# principal.net
KiCad netlist of a schematic drawn in EAGLE
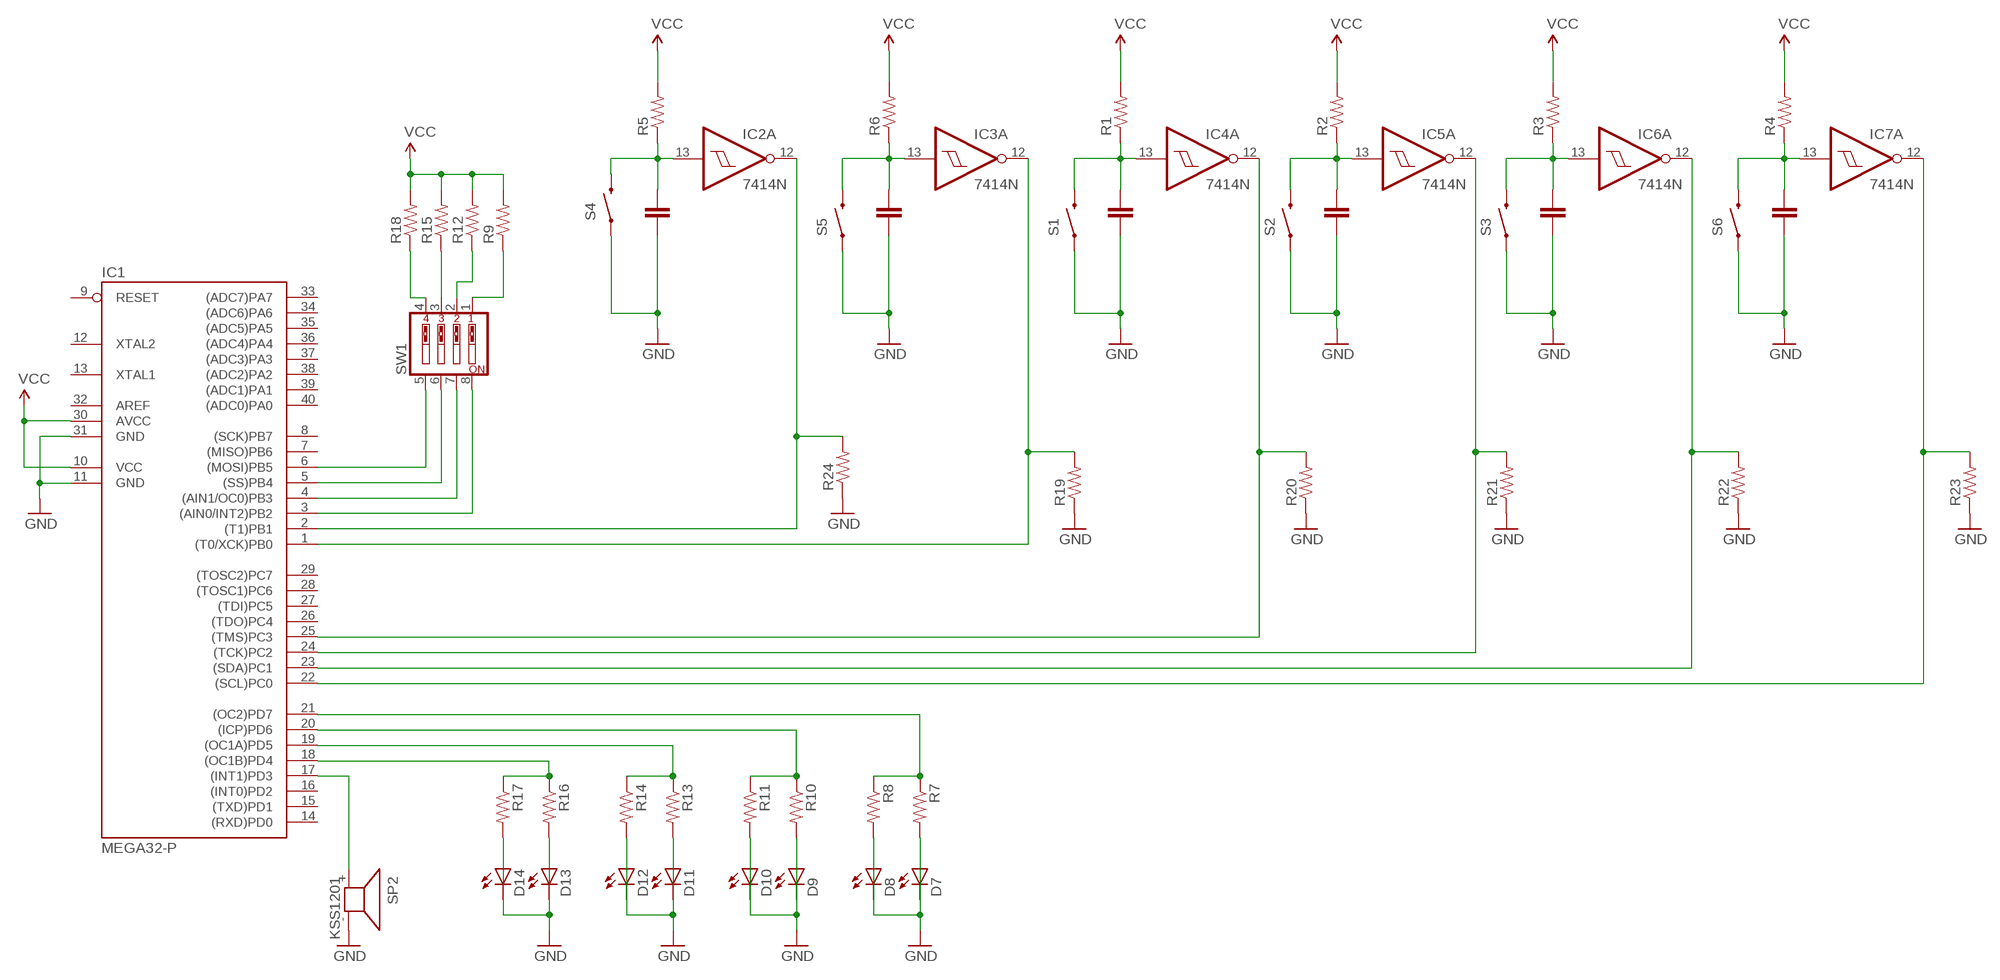
[diagram p0: schematic, sheet 1]

(export (version "E")
  (design (tool "Eeschema 10.0.6"))
  (components
    (comp (ref "D7")
      (value "LED5MM")
      (footprint "eagle-import:LED5MM")
      (libsource (lib "eagle-import") (part "LED5MM"))
    )
    (comp (ref "D8")
      (value "LED5MM")
      (footprint "eagle-import:LED5MM")
      (libsource (lib "eagle-import") (part "LED5MM"))
    )
    (comp (ref "D9")
      (value "LED5MM")
      (footprint "eagle-import:LED5MM")
      (libsource (lib "eagle-import") (part "LED5MM"))
    )
    (comp (ref "D10")
      (value "LED5MM")
      (footprint "eagle-import:LED5MM")
      (libsource (lib "eagle-import") (part "LED5MM"))
    )
    (comp (ref "D11")
      (value "LED5MM")
      (footprint "eagle-import:LED5MM")
      (libsource (lib "eagle-import") (part "LED5MM"))
    )
    (comp (ref "D12")
      (value "LED5MM")
      (footprint "eagle-import:LED5MM")
      (libsource (lib "eagle-import") (part "LED5MM"))
    )
    (comp (ref "D13")
      (value "LED5MM")
      (footprint "eagle-import:LED5MM")
      (libsource (lib "eagle-import") (part "LED5MM"))
    )
    (comp (ref "D14")
      (value "LED5MM")
      (footprint "eagle-import:LED5MM")
      (libsource (lib "eagle-import") (part "LED5MM"))
    )
    (comp (ref "IC1")
      (value "MEGA32-P")
      (footprint "eagle-import:DIL40")
      (fields (field (name "MPN") "ATMEGA32-16PU"))
      (libsource (lib "eagle-import") (part "MEGA32-P"))
    )
    (comp (ref "IC2")
      (value "7414N")
      (footprint "eagle-import:DIL14")
      (libsource (lib "eagle-import") (part "7414N"))
    )
    (comp (ref "IC3")
      (value "7414N")
      (footprint "eagle-import:DIL14")
      (libsource (lib "eagle-import") (part "7414N"))
    )
    (comp (ref "IC4")
      (value "7414N")
      (footprint "eagle-import:DIL14")
      (libsource (lib "eagle-import") (part "7414N"))
    )
    (comp (ref "IC5")
      (value "7414N")
      (footprint "eagle-import:DIL14")
      (libsource (lib "eagle-import") (part "7414N"))
    )
    (comp (ref "IC6")
      (value "7414N")
      (footprint "eagle-import:DIL14")
      (libsource (lib "eagle-import") (part "7414N"))
    )
    (comp (ref "IC7")
      (value "7414N")
      (footprint "eagle-import:DIL14")
      (libsource (lib "eagle-import") (part "7414N"))
    )
    (comp (ref "R1")
      (value "R-US_0204/5")
      (footprint "eagle-import:0204_5")
      (libsource (lib "eagle-import") (part "R-US_0204/5"))
    )
    (comp (ref "R2")
      (value "R-US_0204/5")
      (footprint "eagle-import:0204_5")
      (libsource (lib "eagle-import") (part "R-US_0204/5"))
    )
    (comp (ref "R3")
      (value "R-US_0204/5")
      (footprint "eagle-import:0204_5")
      (libsource (lib "eagle-import") (part "R-US_0204/5"))
    )
    (comp (ref "R4")
      (value "R-US_0204/5")
      (footprint "eagle-import:0204_5")
      (libsource (lib "eagle-import") (part "R-US_0204/5"))
    )
    (comp (ref "R5")
      (value "R-US_0204/5")
      (footprint "eagle-import:0204_5")
      (libsource (lib "eagle-import") (part "R-US_0204/5"))
    )
    (comp (ref "R6")
      (value "R-US_0204/5")
      (footprint "eagle-import:0204_5")
      (libsource (lib "eagle-import") (part "R-US_0204/5"))
    )
    (comp (ref "R7")
      (value "R-US_0204/5")
      (footprint "eagle-import:0204_5")
      (libsource (lib "eagle-import") (part "R-US_0204/5"))
    )
    (comp (ref "R8")
      (value "R-US_0204/5")
      (footprint "eagle-import:0204_5")
      (libsource (lib "eagle-import") (part "R-US_0204/5"))
    )
    (comp (ref "R9")
      (value "R-US_0204/5")
      (footprint "eagle-import:0204_5")
      (libsource (lib "eagle-import") (part "R-US_0204/5"))
    )
    (comp (ref "R10")
      (value "R-US_0204/5")
      (footprint "eagle-import:0204_5")
      (libsource (lib "eagle-import") (part "R-US_0204/5"))
    )
    (comp (ref "R11")
      (value "R-US_0204/5")
      (footprint "eagle-import:0204_5")
      (libsource (lib "eagle-import") (part "R-US_0204/5"))
    )
    (comp (ref "R12")
      (value "R-US_0204/5")
      (footprint "eagle-import:0204_5")
      (libsource (lib "eagle-import") (part "R-US_0204/5"))
    )
    (comp (ref "R13")
      (value "R-US_0204/5")
      (footprint "eagle-import:0204_5")
      (libsource (lib "eagle-import") (part "R-US_0204/5"))
    )
    (comp (ref "R14")
      (value "R-US_0204/5")
      (footprint "eagle-import:0204_5")
      (libsource (lib "eagle-import") (part "R-US_0204/5"))
    )
    (comp (ref "R15")
      (value "R-US_0204/5")
      (footprint "eagle-import:0204_5")
      (libsource (lib "eagle-import") (part "R-US_0204/5"))
    )
    (comp (ref "R16")
      (value "R-US_0204/5")
      (footprint "eagle-import:0204_5")
      (libsource (lib "eagle-import") (part "R-US_0204/5"))
    )
    (comp (ref "R17")
      (value "R-US_0204/5")
      (footprint "eagle-import:0204_5")
      (libsource (lib "eagle-import") (part "R-US_0204/5"))
    )
    (comp (ref "R18")
      (value "R-US_0204/5")
      (footprint "eagle-import:0204_5")
      (libsource (lib "eagle-import") (part "R-US_0204/5"))
    )
    (comp (ref "R19")
      (value "R-US_0204/5")
      (footprint "eagle-import:0204_5")
      (libsource (lib "eagle-import") (part "R-US_0204/5"))
    )
    (comp (ref "R20")
      (value "R-US_0204/5")
      (footprint "eagle-import:0204_5")
      (libsource (lib "eagle-import") (part "R-US_0204/5"))
    )
    (comp (ref "R21")
      (value "R-US_0204/5")
      (footprint "eagle-import:0204_5")
      (libsource (lib "eagle-import") (part "R-US_0204/5"))
    )
    (comp (ref "R22")
      (value "R-US_0204/5")
      (footprint "eagle-import:0204_5")
      (libsource (lib "eagle-import") (part "R-US_0204/5"))
    )
    (comp (ref "R23")
      (value "R-US_0204/5")
      (footprint "eagle-import:0204_5")
      (libsource (lib "eagle-import") (part "R-US_0204/5"))
    )
    (comp (ref "R24")
      (value "R-US_0204/5")
      (footprint "eagle-import:0204_5")
      (libsource (lib "eagle-import") (part "R-US_0204/5"))
    )
    (comp (ref "S1")
      (value "SWITCH-MOMENTARY-2PTH")
      (footprint "eagle-import:TACTILE-PTH")
      (libsource (lib "eagle-import") (part "SWITCH-MOMENTARY-2PTH"))
    )
    (comp (ref "S2")
      (value "SWITCH-MOMENTARY-2PTH")
      (footprint "eagle-import:TACTILE-PTH")
      (libsource (lib "eagle-import") (part "SWITCH-MOMENTARY-2PTH"))
    )
    (comp (ref "S3")
      (value "SWITCH-MOMENTARY-2PTH")
      (footprint "eagle-import:TACTILE-PTH")
      (libsource (lib "eagle-import") (part "SWITCH-MOMENTARY-2PTH"))
    )
    (comp (ref "S4")
      (value "SWITCH-MOMENTARY-2PTH")
      (footprint "eagle-import:TACTILE-PTH")
      (libsource (lib "eagle-import") (part "SWITCH-MOMENTARY-2PTH"))
    )
    (comp (ref "S5")
      (value "SWITCH-MOMENTARY-2PTH")
      (footprint "eagle-import:TACTILE-PTH")
      (libsource (lib "eagle-import") (part "SWITCH-MOMENTARY-2PTH"))
    )
    (comp (ref "S6")
      (value "SWITCH-MOMENTARY-2PTH")
      (footprint "eagle-import:TACTILE-PTH")
      (libsource (lib "eagle-import") (part "SWITCH-MOMENTARY-2PTH"))
    )
    (comp (ref "SP2")
      (value "KSS1201")
      (footprint "eagle-import:KSS1201")
      (libsource (lib "eagle-import") (part "KSS1201"))
    )
    (comp (ref "SW1")
      (value "SW_DIP-4")
      (footprint "eagle-import:EDG-04")
      (libsource (lib "eagle-import") (part "SW_DIP-4"))
    )
  )
  (nets
    (net (code "1") (name "GND") (class "Default")
      (node (ref "D10") (pin "A") (pinfunction "A_A") (pintype "passive"))
      (node (ref "D11") (pin "A") (pinfunction "A_A") (pintype "passive"))
      (node (ref "D12") (pin "A") (pinfunction "A_A") (pintype "passive"))
      (node (ref "D13") (pin "A") (pinfunction "A_A") (pintype "passive"))
      (node (ref "D14") (pin "A") (pinfunction "A_A") (pintype "passive"))
      (node (ref "D7") (pin "A") (pinfunction "A_A") (pintype "passive"))
      (node (ref "D8") (pin "A") (pinfunction "A_A") (pintype "passive"))
      (node (ref "D9") (pin "A") (pinfunction "A_A") (pintype "passive"))
      (node (ref "IC1") (pin "11") (pinfunction "GND_11") (pintype "power_in"))
      (node (ref "IC1") (pin "31") (pinfunction "GND_31") (pintype "power_in"))
      (node (ref "R19") (pin "1") (pinfunction "1_1") (pintype "passive"))
      (node (ref "R20") (pin "1") (pinfunction "1_1") (pintype "passive"))
      (node (ref "R21") (pin "1") (pinfunction "1_1") (pintype "passive"))
      (node (ref "R22") (pin "1") (pinfunction "1_1") (pintype "passive"))
      (node (ref "R23") (pin "1") (pinfunction "1_1") (pintype "passive"))
      (node (ref "R24") (pin "1") (pinfunction "1_1") (pintype "passive"))
      (node (ref "S1") (pin "1") (pinfunction "1_1") (pintype "passive"))
      (node (ref "S2") (pin "1") (pinfunction "1_1") (pintype "passive"))
      (node (ref "S3") (pin "1") (pinfunction "1_1") (pintype "passive"))
      (node (ref "S4") (pin "1") (pinfunction "1_1") (pintype "passive"))
      (node (ref "S5") (pin "1") (pinfunction "1_1") (pintype "passive"))
      (node (ref "S6") (pin "1") (pinfunction "1_1") (pintype "passive"))
      (node (ref "SP2") (pin "-") (pinfunction "2_-") (pintype "passive"))
    )
    (net (code "2") (name "Net-(D7-C)") (class "Default")
      (node (ref "D7") (pin "K") (pinfunction "C_K") (pintype "passive"))
      (node (ref "R7") (pin "2") (pinfunction "2_2") (pintype "passive"))
    )
    (net (code "3") (name "Net-(D8-C)") (class "Default")
      (node (ref "D8") (pin "K") (pinfunction "C_K") (pintype "passive"))
      (node (ref "R8") (pin "2") (pinfunction "2_2") (pintype "passive"))
    )
    (net (code "4") (name "Net-(D9-C)") (class "Default")
      (node (ref "D9") (pin "K") (pinfunction "C_K") (pintype "passive"))
      (node (ref "R10") (pin "2") (pinfunction "2_2") (pintype "passive"))
    )
    (net (code "5") (name "Net-(D10-C)") (class "Default")
      (node (ref "D10") (pin "K") (pinfunction "C_K") (pintype "passive"))
      (node (ref "R11") (pin "2") (pinfunction "2_2") (pintype "passive"))
    )
    (net (code "6") (name "Net-(D11-C)") (class "Default")
      (node (ref "D11") (pin "K") (pinfunction "C_K") (pintype "passive"))
      (node (ref "R13") (pin "2") (pinfunction "2_2") (pintype "passive"))
    )
    (net (code "7") (name "Net-(D12-C)") (class "Default")
      (node (ref "D12") (pin "K") (pinfunction "C_K") (pintype "passive"))
      (node (ref "R14") (pin "2") (pinfunction "2_2") (pintype "passive"))
    )
    (net (code "8") (name "Net-(D13-C)") (class "Default")
      (node (ref "D13") (pin "K") (pinfunction "C_K") (pintype "passive"))
      (node (ref "R16") (pin "2") (pinfunction "2_2") (pintype "passive"))
    )
    (net (code "9") (name "Net-(D14-C)") (class "Default")
      (node (ref "D14") (pin "K") (pinfunction "C_K") (pintype "passive"))
      (node (ref "R17") (pin "2") (pinfunction "2_2") (pintype "passive"))
    )
    (net (code "10") (name "Net-(IC1-(AIN0{slash}INT2)PB2)") (class "Default")
      (node (ref "IC1") (pin "3") (pinfunction "(AIN0/INT2)PB2_3") (pintype "bidirectional"))
      (node (ref "SW1") (pin "8") (pinfunction "8_8") (pintype "passive"))
    )
    (net (code "11") (name "Net-(IC1-(AIN1{slash}OC0)PB3)") (class "Default")
      (node (ref "IC1") (pin "4") (pinfunction "(AIN1/OC0)PB3_4") (pintype "bidirectional"))
      (node (ref "SW1") (pin "7") (pinfunction "7_7") (pintype "passive"))
    )
    (net (code "12") (name "Net-(IC1-(ICP)PD6)") (class "Default")
      (node (ref "IC1") (pin "20") (pinfunction "(ICP)PD6_20") (pintype "bidirectional"))
      (node (ref "R10") (pin "1") (pinfunction "1_1") (pintype "passive"))
      (node (ref "R11") (pin "1") (pinfunction "1_1") (pintype "passive"))
    )
    (net (code "13") (name "Net-(IC1-(INT1)PD3)") (class "Default")
      (node (ref "IC1") (pin "17") (pinfunction "(INT1)PD3_17") (pintype "bidirectional"))
      (node (ref "SP2") (pin "+") (pinfunction "1_+") (pintype "passive"))
    )
    (net (code "14") (name "Net-(IC1-(MOSI)PB5)") (class "Default")
      (node (ref "IC1") (pin "6") (pinfunction "(MOSI)PB5_6") (pintype "bidirectional"))
      (node (ref "SW1") (pin "5") (pinfunction "5_5") (pintype "passive"))
    )
    (net (code "15") (name "Net-(IC1-(OC1A)PD5)") (class "Default")
      (node (ref "IC1") (pin "19") (pinfunction "(OC1A)PD5_19") (pintype "bidirectional"))
      (node (ref "R13") (pin "1") (pinfunction "1_1") (pintype "passive"))
      (node (ref "R14") (pin "1") (pinfunction "1_1") (pintype "passive"))
    )
    (net (code "16") (name "Net-(IC1-(OC1B)PD4)") (class "Default")
      (node (ref "IC1") (pin "18") (pinfunction "(OC1B)PD4_18") (pintype "bidirectional"))
      (node (ref "R16") (pin "1") (pinfunction "1_1") (pintype "passive"))
      (node (ref "R17") (pin "1") (pinfunction "1_1") (pintype "passive"))
    )
    (net (code "17") (name "Net-(IC1-(OC2)PD7)") (class "Default")
      (node (ref "IC1") (pin "21") (pinfunction "(OC2)PD7_21") (pintype "bidirectional"))
      (node (ref "R7") (pin "1") (pinfunction "1_1") (pintype "passive"))
      (node (ref "R8") (pin "1") (pinfunction "1_1") (pintype "passive"))
    )
    (net (code "18") (name "Net-(IC1-(SCL)PC0)") (class "Default")
      (node (ref "IC1") (pin "22") (pinfunction "(SCL)PC0_22") (pintype "bidirectional"))
      (node (ref "IC7") (pin "12") (pinfunction "O_12") (pintype "output"))
      (node (ref "R23") (pin "2") (pinfunction "2_2") (pintype "passive"))
    )
    (net (code "19") (name "Net-(IC1-(SDA)PC1)") (class "Default")
      (node (ref "IC1") (pin "23") (pinfunction "(SDA)PC1_23") (pintype "bidirectional"))
      (node (ref "IC6") (pin "12") (pinfunction "O_12") (pintype "output"))
      (node (ref "R22") (pin "2") (pinfunction "2_2") (pintype "passive"))
    )
    (net (code "20") (name "Net-(IC1-(SS)PB4)") (class "Default")
      (node (ref "IC1") (pin "5") (pinfunction "(SS)PB4_5") (pintype "bidirectional"))
      (node (ref "SW1") (pin "6") (pinfunction "6_6") (pintype "passive"))
    )
    (net (code "21") (name "Net-(IC1-(T0{slash}XCK)PB0)") (class "Default")
      (node (ref "IC1") (pin "1") (pinfunction "(T0/XCK)PB0_1") (pintype "bidirectional"))
      (node (ref "IC3") (pin "12") (pinfunction "O_12") (pintype "output"))
      (node (ref "R19") (pin "2") (pinfunction "2_2") (pintype "passive"))
    )
    (net (code "22") (name "Net-(IC1-(T1)PB1)") (class "Default")
      (node (ref "IC1") (pin "2") (pinfunction "(T1)PB1_2") (pintype "bidirectional"))
      (node (ref "IC2") (pin "12") (pinfunction "O_12") (pintype "output"))
      (node (ref "R24") (pin "2") (pinfunction "2_2") (pintype "passive"))
    )
    (net (code "23") (name "Net-(IC1-(TCK)PC2)") (class "Default")
      (node (ref "IC1") (pin "24") (pinfunction "(TCK)PC2_24") (pintype "bidirectional"))
      (node (ref "IC5") (pin "12") (pinfunction "O_12") (pintype "output"))
      (node (ref "R21") (pin "2") (pinfunction "2_2") (pintype "passive"))
    )
    (net (code "24") (name "Net-(IC1-(TMS)PC3)") (class "Default")
      (node (ref "IC1") (pin "25") (pinfunction "(TMS)PC3_25") (pintype "bidirectional"))
      (node (ref "IC4") (pin "12") (pinfunction "O_12") (pintype "output"))
      (node (ref "R20") (pin "2") (pinfunction "2_2") (pintype "passive"))
    )
    (net (code "25") (name "Net-(IC2A-I)") (class "Default")
      (node (ref "IC2") (pin "13") (pinfunction "I_13") (pintype "input"))
      (node (ref "R5") (pin "1") (pinfunction "1_1") (pintype "passive"))
      (node (ref "S4") (pin "3") (pinfunction "2_3") (pintype "passive"))
    )
    (net (code "26") (name "Net-(IC3A-I)") (class "Default")
      (node (ref "IC3") (pin "13") (pinfunction "I_13") (pintype "input"))
      (node (ref "R6") (pin "1") (pinfunction "1_1") (pintype "passive"))
      (node (ref "S5") (pin "3") (pinfunction "2_3") (pintype "passive"))
    )
    (net (code "27") (name "Net-(IC4A-I)") (class "Default")
      (node (ref "IC4") (pin "13") (pinfunction "I_13") (pintype "input"))
      (node (ref "R1") (pin "1") (pinfunction "1_1") (pintype "passive"))
      (node (ref "S1") (pin "3") (pinfunction "2_3") (pintype "passive"))
    )
    (net (code "28") (name "Net-(IC5A-I)") (class "Default")
      (node (ref "IC5") (pin "13") (pinfunction "I_13") (pintype "input"))
      (node (ref "R2") (pin "1") (pinfunction "1_1") (pintype "passive"))
      (node (ref "S2") (pin "3") (pinfunction "2_3") (pintype "passive"))
    )
    (net (code "29") (name "Net-(IC6A-I)") (class "Default")
      (node (ref "IC6") (pin "13") (pinfunction "I_13") (pintype "input"))
      (node (ref "R3") (pin "1") (pinfunction "1_1") (pintype "passive"))
      (node (ref "S3") (pin "3") (pinfunction "2_3") (pintype "passive"))
    )
    (net (code "30") (name "Net-(IC7A-I)") (class "Default")
      (node (ref "IC7") (pin "13") (pinfunction "I_13") (pintype "input"))
      (node (ref "R4") (pin "1") (pinfunction "1_1") (pintype "passive"))
      (node (ref "S6") (pin "3") (pinfunction "2_3") (pintype "passive"))
    )
    (net (code "31") (name "Net-(R9-Pad1)") (class "Default")
      (node (ref "R9") (pin "1") (pinfunction "1_1") (pintype "passive"))
      (node (ref "SW1") (pin "1") (pinfunction "1_1") (pintype "passive"))
    )
    (net (code "32") (name "Net-(R12-Pad1)") (class "Default")
      (node (ref "R12") (pin "1") (pinfunction "1_1") (pintype "passive"))
      (node (ref "SW1") (pin "2") (pinfunction "2_2") (pintype "passive"))
    )
    (net (code "33") (name "Net-(R15-Pad1)") (class "Default")
      (node (ref "R15") (pin "1") (pinfunction "1_1") (pintype "passive"))
      (node (ref "SW1") (pin "3") (pinfunction "3_3") (pintype "passive"))
    )
    (net (code "34") (name "Net-(R18-Pad1)") (class "Default")
      (node (ref "R18") (pin "1") (pinfunction "1_1") (pintype "passive"))
      (node (ref "SW1") (pin "4") (pinfunction "4_4") (pintype "passive"))
    )
    (net (code "35") (name "VCC") (class "Default")
      (node (ref "IC1") (pin "10") (pinfunction "VCC_10") (pintype "power_in"))
      (node (ref "IC1") (pin "30") (pinfunction "AVCC_30") (pintype "power_in"))
      (node (ref "R1") (pin "2") (pinfunction "2_2") (pintype "passive"))
      (node (ref "R12") (pin "2") (pinfunction "2_2") (pintype "passive"))
      (node (ref "R15") (pin "2") (pinfunction "2_2") (pintype "passive"))
      (node (ref "R18") (pin "2") (pinfunction "2_2") (pintype "passive"))
      (node (ref "R2") (pin "2") (pinfunction "2_2") (pintype "passive"))
      (node (ref "R3") (pin "2") (pinfunction "2_2") (pintype "passive"))
      (node (ref "R4") (pin "2") (pinfunction "2_2") (pintype "passive"))
      (node (ref "R5") (pin "2") (pinfunction "2_2") (pintype "passive"))
      (node (ref "R6") (pin "2") (pinfunction "2_2") (pintype "passive"))
      (node (ref "R9") (pin "2") (pinfunction "2_2") (pintype "passive"))
    )
    (net (code "36") (name "unconnected-(IC1-(ADC0)PA0-Pad40)") (class "Default")
      (node (ref "IC1") (pin "40") (pinfunction "(ADC0)PA0_40") (pintype "bidirectional"))
    )
    (net (code "37") (name "unconnected-(IC1-(ADC1)PA1-Pad39)") (class "Default")
      (node (ref "IC1") (pin "39") (pinfunction "(ADC1)PA1_39") (pintype "bidirectional"))
    )
    (net (code "38") (name "unconnected-(IC1-(ADC2)PA2-Pad38)") (class "Default")
      (node (ref "IC1") (pin "38") (pinfunction "(ADC2)PA2_38") (pintype "bidirectional"))
    )
    (net (code "39") (name "unconnected-(IC1-(ADC3)PA3-Pad37)") (class "Default")
      (node (ref "IC1") (pin "37") (pinfunction "(ADC3)PA3_37") (pintype "bidirectional"))
    )
    (net (code "40") (name "unconnected-(IC1-(ADC4)PA4-Pad36)") (class "Default")
      (node (ref "IC1") (pin "36") (pinfunction "(ADC4)PA4_36") (pintype "bidirectional"))
    )
    (net (code "41") (name "unconnected-(IC1-(ADC5)PA5-Pad35)") (class "Default")
      (node (ref "IC1") (pin "35") (pinfunction "(ADC5)PA5_35") (pintype "bidirectional"))
    )
    (net (code "42") (name "unconnected-(IC1-(ADC6)PA6-Pad34)") (class "Default")
      (node (ref "IC1") (pin "34") (pinfunction "(ADC6)PA6_34") (pintype "bidirectional"))
    )
    (net (code "43") (name "unconnected-(IC1-(ADC7)PA7-Pad33)") (class "Default")
      (node (ref "IC1") (pin "33") (pinfunction "(ADC7)PA7_33") (pintype "bidirectional"))
    )
    (net (code "44") (name "unconnected-(IC1-(INT0)PD2-Pad16)") (class "Default")
      (node (ref "IC1") (pin "16") (pinfunction "(INT0)PD2_16") (pintype "bidirectional"))
    )
    (net (code "45") (name "unconnected-(IC1-(MISO)PB6-Pad7)") (class "Default")
      (node (ref "IC1") (pin "7") (pinfunction "(MISO)PB6_7") (pintype "bidirectional"))
    )
    (net (code "46") (name "unconnected-(IC1-(RXD)PD0-Pad14)") (class "Default")
      (node (ref "IC1") (pin "14") (pinfunction "(RXD)PD0_14") (pintype "bidirectional"))
    )
    (net (code "47") (name "unconnected-(IC1-(SCK)PB7-Pad8)") (class "Default")
      (node (ref "IC1") (pin "8") (pinfunction "(SCK)PB7_8") (pintype "bidirectional"))
    )
    (net (code "48") (name "unconnected-(IC1-(TDI)PC5-Pad27)") (class "Default")
      (node (ref "IC1") (pin "27") (pinfunction "(TDI)PC5_27") (pintype "bidirectional"))
    )
    (net (code "49") (name "unconnected-(IC1-(TDO)PC4-Pad26)") (class "Default")
      (node (ref "IC1") (pin "26") (pinfunction "(TDO)PC4_26") (pintype "bidirectional"))
    )
    (net (code "50") (name "unconnected-(IC1-(TOSC1)PC6-Pad28)") (class "Default")
      (node (ref "IC1") (pin "28") (pinfunction "(TOSC1)PC6_28") (pintype "bidirectional"))
    )
    (net (code "51") (name "unconnected-(IC1-(TOSC2)PC7-Pad29)") (class "Default")
      (node (ref "IC1") (pin "29") (pinfunction "(TOSC2)PC7_29") (pintype "bidirectional"))
    )
    (net (code "52") (name "unconnected-(IC1-(TXD)PD1-Pad15)") (class "Default")
      (node (ref "IC1") (pin "15") (pinfunction "(TXD)PD1_15") (pintype "bidirectional"))
    )
    (net (code "53") (name "unconnected-(IC1-AREF-Pad32)") (class "Default")
      (node (ref "IC1") (pin "32") (pinfunction "AREF_32") (pintype "passive"))
    )
    (net (code "54") (name "unconnected-(IC1-RESET-Pad9)") (class "Default")
      (node (ref "IC1") (pin "9") (pinfunction "RESET_9") (pintype "input"))
    )
    (net (code "55") (name "unconnected-(IC1-XTAL1-Pad13)") (class "Default")
      (node (ref "IC1") (pin "13") (pinfunction "XTAL1_13") (pintype "bidirectional"))
    )
    (net (code "56") (name "unconnected-(IC1-XTAL2-Pad12)") (class "Default")
      (node (ref "IC1") (pin "12") (pinfunction "XTAL2_12") (pintype "bidirectional"))
    )
  )
)
